# Top_sheet.net
KiCad netlist of a schematic drawn in Altium Designer
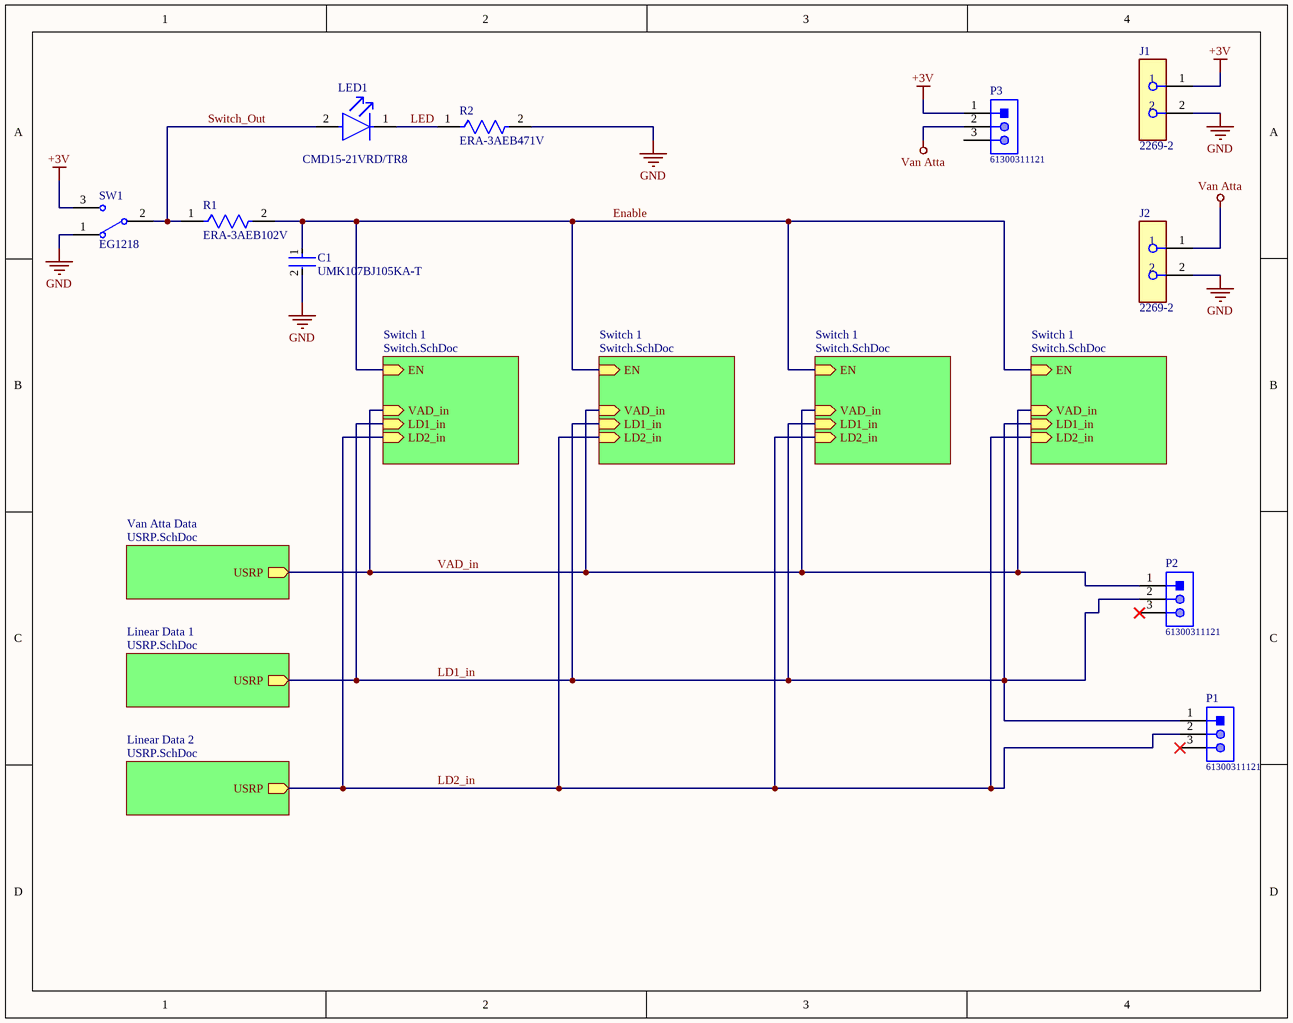
[diagram p0: Top sheet.SchDoc]

(export (version "E")
  (design (tool "Eeschema 10.0.6"))
  (components
    (comp (ref "C1")
      (value "UMK107BJ105KA-T")
      (footprint "FP-0603-L_1_6_0_1-W_0_8_0-IPC_A")
      (description "None")
      (fields (field (name "TOLERANCE") "10%"))
      (libsource (lib "Altium Content Vault") (part "02cd4be3c70576c341d710602a673aa"))
    )
    (comp (ref "J1")
      (value "2269-2")
      (footprint "FP-2269-2-MFG")
      (description "CONN DBL BANANA JACK TURRET")
      (libsource (lib "Altium Content Vault") (part "3ddab50f66188bb7952c54a1b76274c"))
    )
    (comp (ref "J2")
      (value "2269-2")
      (footprint "FP-2269-2-MFG")
      (description "CONN DBL BANANA JACK TURRET")
      (libsource (lib "Altium Content Vault") (part "3ddab50f66188bb7952c54a1b76274c"))
    )
    (comp (ref "LED1")
      (value "CMD15-21VRD/TR8")
      (footprint "FP-CMD15-21-MFG")
      (description "LED RED DIFFUSED 1206 SMD")
      (fields
        (field (name "MANUFACTURER") "VCC")
        (field (name "OCTOPART") "https://octopart.com/cmd15-21vrd%2Ftr8-vcc-26668835")
      )
      (libsource (lib "Altium Content Vault") (part "8706943c75ba83719d021d2fdc84c58"))
    )
    (comp (ref "P1")
      (value "61300311121")
      (footprint "61300311121")
      (description "THT Vertical Pin Header WR-PHD, Pitch 2.54 mm, Single Row, 3 pins")
      (fields (field (name "MANUFACTURER") "Wurth Elektronik") (field (name "PUBLISHER") "WurthElektronik"))
      (libsource (lib "Altium Content Vault") (part "WE-CN-1P-M-R3"))
    )
    (comp (ref "P2")
      (value "61300311121")
      (footprint "61300311121")
      (description "THT Vertical Pin Header WR-PHD, Pitch 2.54 mm, Single Row, 3 pins")
      (fields (field (name "MANUFACTURER") "Wurth Elektronik") (field (name "PUBLISHER") "WurthElektronik"))
      (libsource (lib "Altium Content Vault") (part "WE-CN-1P-M-R3"))
    )
    (comp (ref "P3")
      (value "61300311121")
      (footprint "61300311121")
      (description "THT Vertical Pin Header WR-PHD, Pitch 2.54 mm, Single Row, 3 pins")
      (fields (field (name "MANUFACTURER") "Wurth Elektronik") (field (name "PUBLISHER") "WurthElektronik"))
      (libsource (lib "Altium Content Vault") (part "WE-CN-1P-M-R3"))
    )
    (comp (ref "R1")
      (value "ERA-3AEB102V")
      (footprint "FP-ERA3A-IPC_C")
      (description "RES SMD 1K OHM 0.1% 1/10W 0603")
      (fields (field (name "TOLERANCE") "0.1%"))
      (libsource (lib "Altium Content Vault") (part "1029c3af85768c4190bb7ad29bc67b5"))
    )
    (comp (ref "R2")
      (value "ERA-3AEB471V")
      (footprint "FP-ERA3A-IPC_A")
      (description "RES SMD 470 OHM 0.1% 1/10W 0603")
      (fields (field (name "TOLERANCE") "0.1%"))
      (libsource (lib "Altium Content Vault") (part "8db39607336c341a927600551d01821"))
    )
    (comp (ref "SW1")
      (value "EG1218")
      (footprint "ESWI-EG1218_V")
      (description "Slide Switch, SPDT, 500 V, -20 to 70 degC, 3-Pin THD, RoHS, Bulk")
      (fields (field (name "MANUFACTURER") "E-Switch"))
      (libsource (lib "Nick") (part "SW-SPDT-3_B"))
    )
  )
  (nets
    (net (code "1") (name "+3V") (class "Default")
      (node (ref "J1") (pin "1") (pinfunction "1_1") (pintype "passive"))
      (node (ref "P3") (pin "1") (pinfunction "1_1") (pintype "passive"))
      (node (ref "SW1") (pin "3") (pinfunction "3_3") (pintype "passive"))
    )
    (net (code "2") (name "/Enable") (class "Default")
      (node (ref "C1") (pin "1") (pinfunction "1_1") (pintype "passive"))
      (node (ref "R1") (pin "2") (pinfunction "2_2") (pintype "passive"))
    )
    (net (code "3") (name "/LD1_in") (class "Default")
      (node (ref "P1") (pin "1") (pinfunction "1_1") (pintype "passive"))
      (node (ref "P2") (pin "2") (pinfunction "2_2") (pintype "passive"))
    )
    (net (code "4") (name "/LD2_in") (class "Default")
      (node (ref "P1") (pin "2") (pinfunction "2_2") (pintype "passive"))
    )
    (net (code "5") (name "/LED") (class "Default")
      (node (ref "LED1") (pin "1") (pinfunction "C_1") (pintype "passive"))
      (node (ref "R2") (pin "1") (pinfunction "1_1") (pintype "passive"))
    )
    (net (code "6") (name "/Switch_Out") (class "Default")
      (node (ref "LED1") (pin "2") (pinfunction "A_2") (pintype "passive"))
      (node (ref "R1") (pin "1") (pinfunction "1_1") (pintype "passive"))
      (node (ref "SW1") (pin "2") (pinfunction "COM_2") (pintype "passive"))
    )
    (net (code "7") (name "/VAD_in") (class "Default")
      (node (ref "P2") (pin "1") (pinfunction "1_1") (pintype "passive"))
    )
    (net (code "8") (name "GND") (class "Default")
      (node (ref "C1") (pin "2") (pinfunction "2_2") (pintype "passive"))
      (node (ref "J1") (pin "2") (pinfunction "2_2") (pintype "passive"))
      (node (ref "J2") (pin "2") (pinfunction "2_2") (pintype "passive"))
      (node (ref "R2") (pin "2") (pinfunction "2_2") (pintype "passive"))
      (node (ref "SW1") (pin "1") (pinfunction "1_1") (pintype "passive"))
    )
    (net (code "9") (name "Van Atta") (class "Default")
      (node (ref "J2") (pin "1") (pinfunction "1_1") (pintype "passive"))
      (node (ref "P3") (pin "2") (pinfunction "2_2") (pintype "passive"))
    )
    (net (code "10") (name "unconnected-(P1-Pad3)") (class "Default")
      (node (ref "P1") (pin "3") (pinfunction "3_3") (pintype "passive+no_connect"))
    )
    (net (code "11") (name "unconnected-(P2-Pad3)") (class "Default")
      (node (ref "P2") (pin "3") (pinfunction "3_3") (pintype "passive+no_connect"))
    )
    (net (code "12") (name "unconnected-(P3-Pad3)") (class "Default")
      (node (ref "P3") (pin "3") (pinfunction "3_3") (pintype "passive"))
    )
  )
)
